# Sheet_1_2023-01-11.net
KiCad netlist of a schematic drawn in Altium Designer
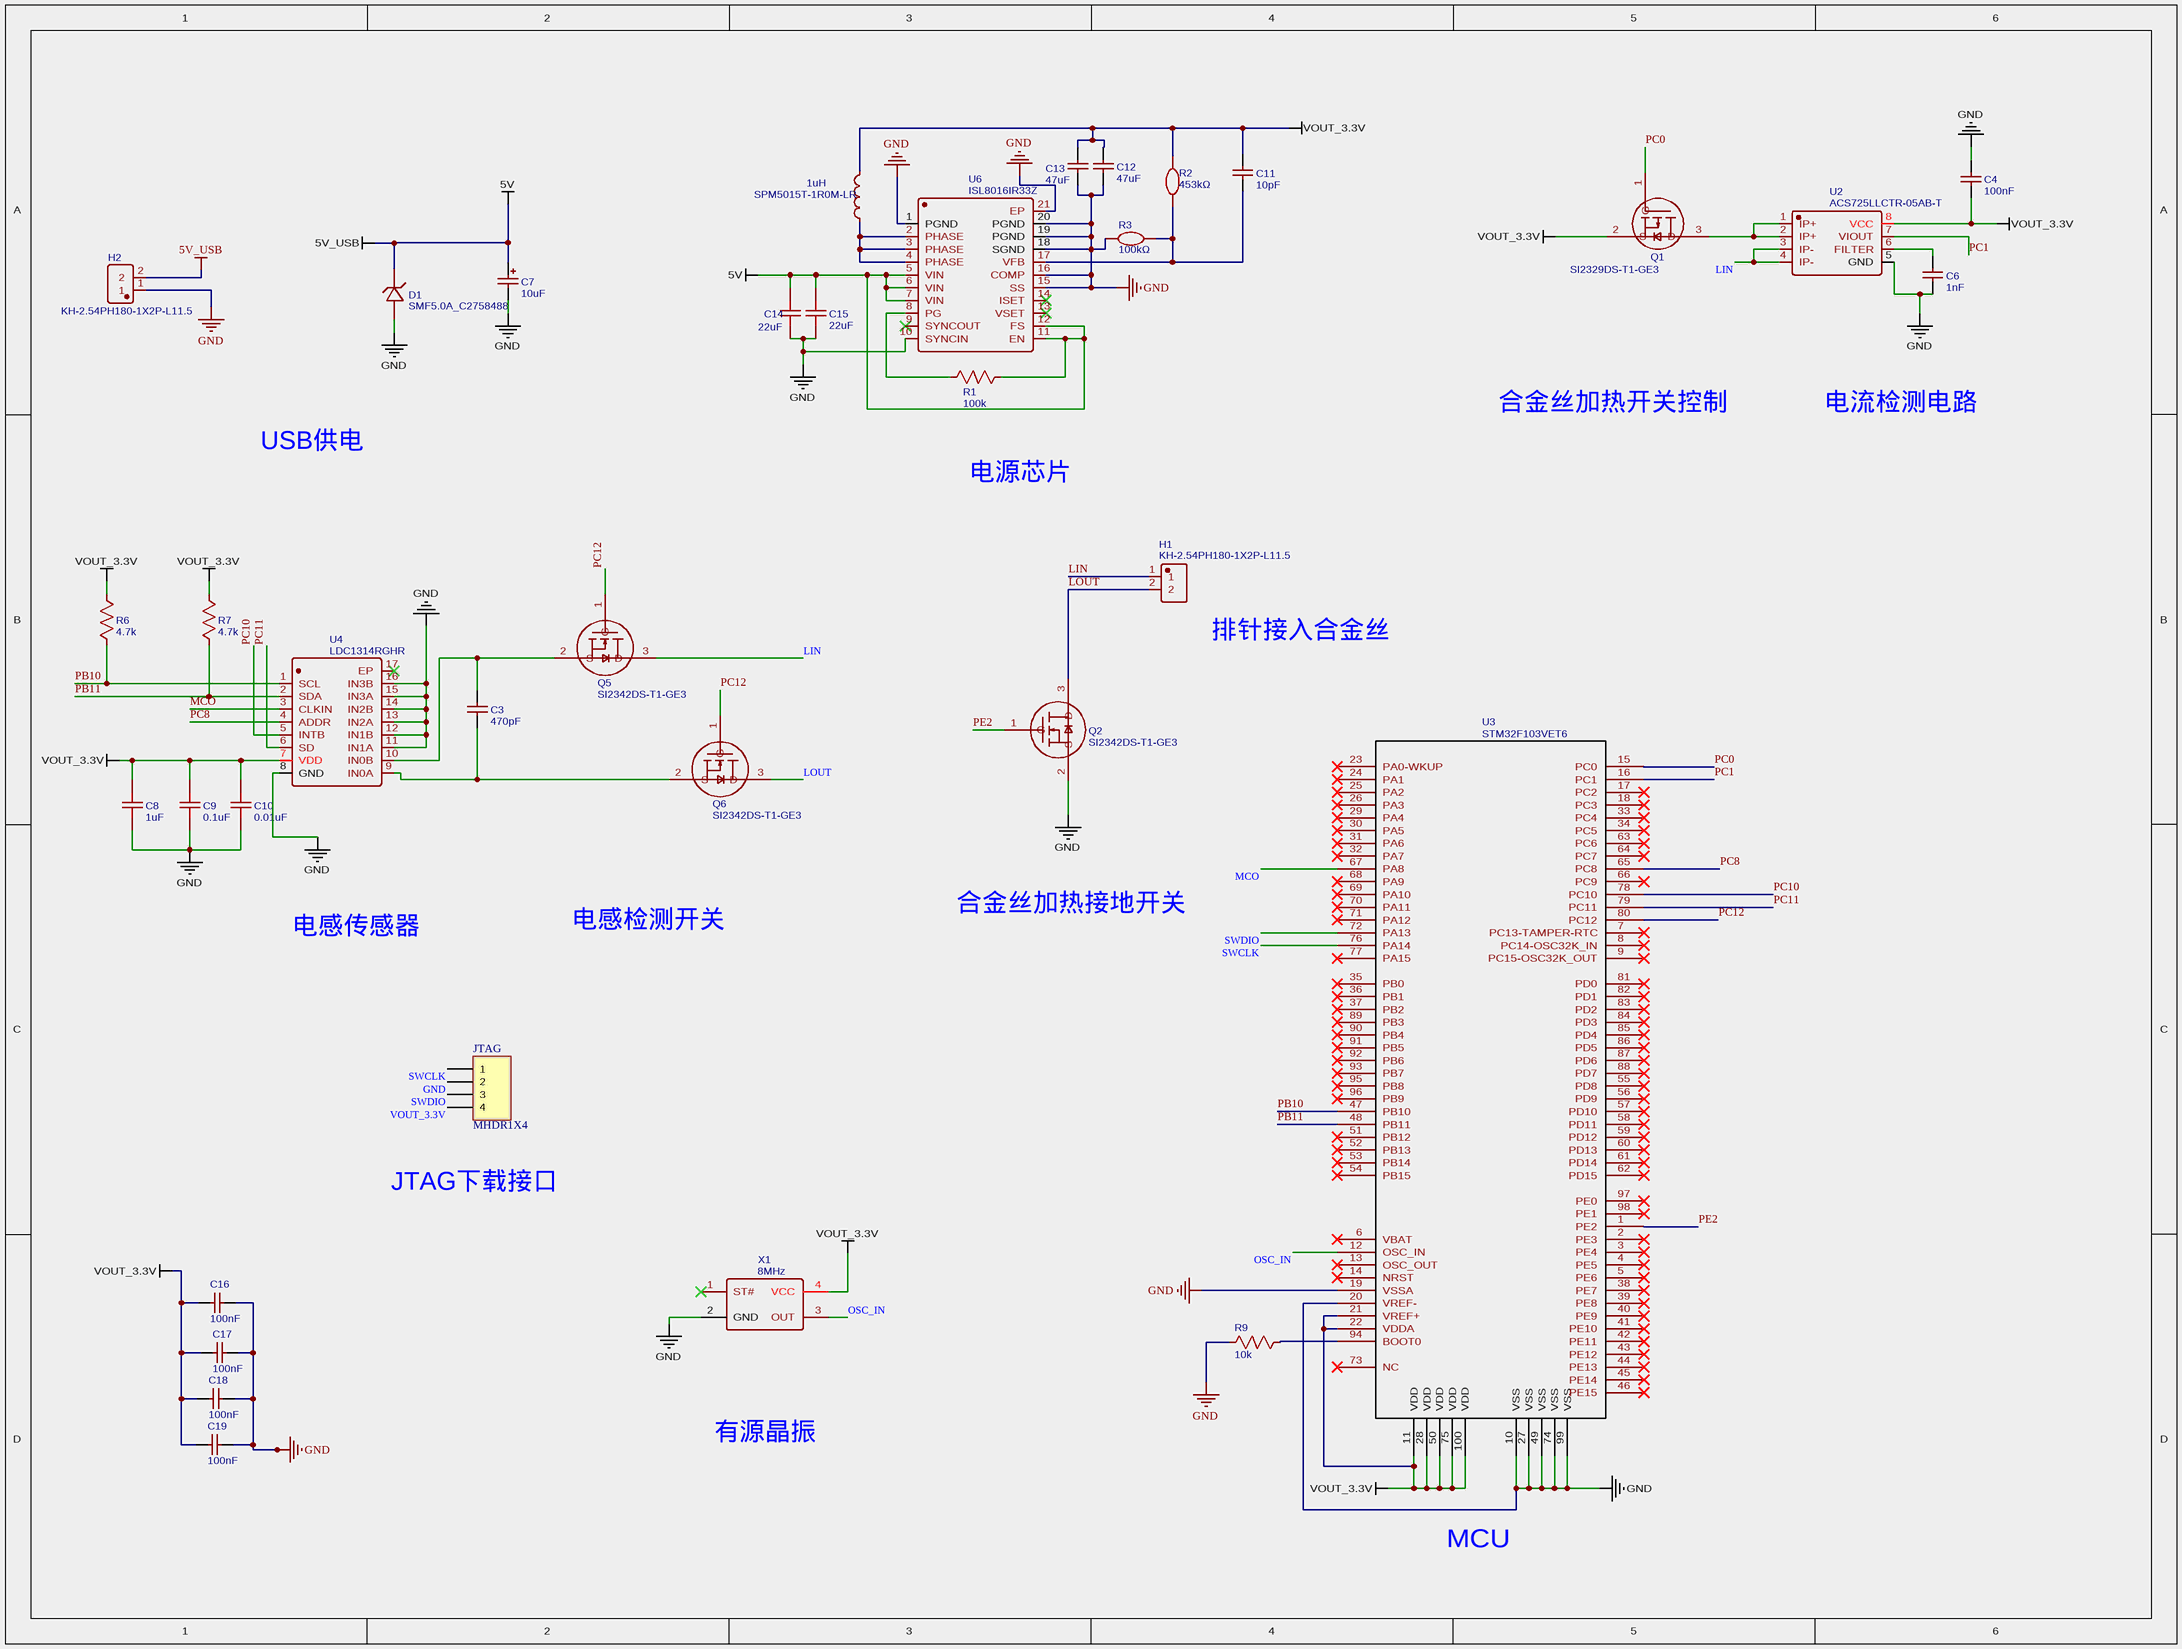
[diagram p0: Sheet_1_2023-01-11.schdoc]

(export (version "E")
  (design (tool "Eeschema 10.0.6"))
  (components
    (comp (ref "1uH")
      (value "SPM5015T-1R0M-LR")
      (footprint "IND-SMD_L5.4-W5.1_SPM5020")
      (fields (field (name "BOM_SUPPLIER PART") "C1329923") (field (name "CONTRIBUTOR") "LCSC"))
      (libsource (lib "altium-import") (part "root_1_SPM5015T-1R0M-LR_"))
    )
    (comp (ref "C3")
      (value "470pF")
      (footprint "C0603")
      (fields
        (field (name "BOM_MANUFACTURER PART") "CC0603KRX7R9BB471")
        (field (name "BOM_SUPPLIER PART") "C107092")
      )
      (libsource (lib "altium-import") (part "root_1_470pF_"))
    )
    (comp (ref "C4")
      (value "100nF")
      (footprint "C0402_NEW")
      (fields
        (field (name "BOM_MANUFACTURER PART") "CL05B104KO5NNNC")
        (field (name "BOM_SUPPLIER PART") "C1525")
      )
      (libsource (lib "altium-import") (part "root_1_100nF_"))
    )
    (comp (ref "C6")
      (value "1nF")
      (footprint "C0603")
      (fields
        (field (name "BOM_MANUFACTURER PART") "CC0603KRX7R9BB102")
        (field (name "BOM_SUPPLIER PART") "C100040")
      )
      (libsource (lib "altium-import") (part "root_1_1nF_"))
    )
    (comp (ref "C7")
      (value "10uF")
      (footprint "CASE-A_3216")
      (fields
        (field (name "BOM_MANUFACTURER PART") "TAJA106K010RNJ")
        (field (name "BOM_SUPPLIER PART") "C7177")
      )
      (libsource (lib "altium-import") (part "root_3_10uF_"))
    )
    (comp (ref "C8")
      (value "1uF")
      (footprint "C0603")
      (fields (field (name "CONTRIBUTOR") "LCEDA_Lib"))
      (libsource (lib "altium-import") (part "root_1_1u_"))
    )
    (comp (ref "C9")
      (value "0.1uF")
      (footprint "C0603")
      (fields (field (name "CONTRIBUTOR") "LCEDA_Lib"))
      (libsource (lib "altium-import") (part "root_1_0.1u_"))
    )
    (comp (ref "C10")
      (value "0.01uF")
      (footprint "C0603")
      (fields (field (name "CONTRIBUTOR") "LCEDA_Lib"))
      (libsource (lib "altium-import") (part "root_1_0.01u_"))
    )
    (comp (ref "C11")
      (value "10pF")
      (footprint "C0402")
      (fields
        (field (name "BOM_MANUFACTURER PART") "CC0402JRNPO9BN100")
        (field (name "BOM_SUPPLIER PART") "C106199")
      )
      (libsource (lib "altium-import") (part "root_3_10pF_"))
    )
    (comp (ref "C12")
      (value "47uF")
      (footprint "C0805")
      (fields
        (field (name "BOM_MANUFACTURER PART") "CL21A476MQYNNNE")
        (field (name "BOM_SUPPLIER PART") "C16780")
      )
      (libsource (lib "altium-import") (part "root_1_47uF_"))
    )
    (comp (ref "C13")
      (value "47uF")
      (footprint "C0805")
      (fields
        (field (name "BOM_MANUFACTURER PART") "CL21A476MQYNNNE")
        (field (name "BOM_SUPPLIER PART") "C16780")
      )
      (libsource (lib "altium-import") (part "root_1_47uF_"))
    )
    (comp (ref "C14")
      (value "22uF")
      (footprint "C0603")
      (fields
        (field (name "BOM_MANUFACTURER PART") "CL10A226MQ8NRNC")
        (field (name "BOM_SUPPLIER PART") "C59461")
      )
      (libsource (lib "altium-import") (part "root_1_22uF_"))
    )
    (comp (ref "C15")
      (value "22uF")
      (footprint "C0603")
      (fields
        (field (name "BOM_MANUFACTURER PART") "CL10A226MQ8NRNC")
        (field (name "BOM_SUPPLIER PART") "C59461")
      )
      (libsource (lib "altium-import") (part "root_1_22uF_"))
    )
    (comp (ref "C16")
      (value "100nF")
      (footprint "C0402_NEW")
      (fields
        (field (name "BOM_MANUFACTURER PART") "CL05B104KO5NNNC")
        (field (name "BOM_SUPPLIER PART") "C1525")
      )
      (libsource (lib "DCDC_schlib_2023-01-11") (part "100nF"))
    )
    (comp (ref "C17")
      (value "100nF")
      (footprint "C0402_NEW")
      (fields
        (field (name "BOM_MANUFACTURER PART") "CL05B104KO5NNNC")
        (field (name "BOM_SUPPLIER PART") "C1525")
      )
      (libsource (lib "DCDC_schlib_2023-01-11") (part "100nF"))
    )
    (comp (ref "C18")
      (value "100nF")
      (footprint "C0402_NEW")
      (fields
        (field (name "BOM_MANUFACTURER PART") "CL05B104KO5NNNC")
        (field (name "BOM_SUPPLIER PART") "C1525")
      )
      (libsource (lib "DCDC_schlib_2023-01-11") (part "100nF"))
    )
    (comp (ref "C19")
      (value "100nF")
      (footprint "C0402_NEW")
      (fields
        (field (name "BOM_MANUFACTURER PART") "CL05B104KO5NNNC")
        (field (name "BOM_SUPPLIER PART") "C1525")
      )
      (libsource (lib "DCDC_schlib_2023-01-11") (part "100nF"))
    )
    (comp (ref "D1")
      (value "SMF5.0A_C2758488")
      (footprint "SOD-123FL_L2.7-W1.8-LS3.7-RD")
      (fields
        (field (name "BOM_SUPPLIER PART") "C2758488")
        (field (name "BOM_MANUFACTURER PART") "SMF5.0A")
        (field (name "CONTRIBUTOR") "LCSC")
      )
      (libsource (lib "altium-import") (part "root_3_SMF5.0A_C2758488_"))
    )
    (comp (ref "H1")
      (value "KH-2.54PH180-1X2P-L11.5")
      (footprint "HDR-TH_2P-P2.54-V-M")
      (fields (field (name "BOM_SUPPLIER PART") "C2905434") (field (name "CONTRIBUTOR") "LCSC"))
      (libsource (lib "altium-import") (part "root_0_KH-2.54PH180-1X2P-L11.5_"))
    )
    (comp (ref "H2")
      (value "KH-2.54PH180-1X2P-L11.5")
      (footprint "HDR-TH_2P-P2.54-V-M")
      (fields (field (name "BOM_SUPPLIER PART") "C2905434") (field (name "CONTRIBUTOR") "LCSC"))
      (libsource (lib "altium-import") (part "root_2_KH-2.54PH180-1X2P-L11.5_"))
    )
    (comp (ref "JTAG")
      (value "MHDR1X4")
      (footprint "MHDR1X4")
      (description "Header, 4-Pin")
      (fields (field (name "PUBLISHER") "Altium Limited"))
      (libsource (lib "Miscellaneous Connectors") (part "MHDR1X4"))
    )
    (comp (ref "Q1")
      (value "SI2329DS-T1-GE3")
      (footprint "SOT-23_L2.9-W1.3-P1.90-LS2.4-BR")
      (fields (field (name "BOM_SUPPLIER PART") "C85167") (field (name "CONTRIBUTOR") "LCSC"))
      (libsource (lib "altium-import") (part "root_3_SI2329DS-T1-GE3_"))
    )
    (comp (ref "Q2")
      (value "SI2342DS-T1-GE3")
      (footprint "SOT-23_L2.9-W1.3-P1.90-LS2.4-BR")
      (fields (field (name "BOM_SUPPLIER PART") "C142553") (field (name "CONTRIBUTOR") "LCSC"))
      (libsource (lib "altium-import") (part "root_0_SI2342DS-T1-GE3_"))
    )
    (comp (ref "Q5")
      (value "SI2342DS-T1-GE3")
      (footprint "SOT-23_L2.9-W1.3-P1.90-LS2.4-BR")
      (fields (field (name "BOM_SUPPLIER PART") "C142553") (field (name "CONTRIBUTOR") "LCSC"))
      (libsource (lib "altium-import") (part "root_3_SI2342DS-T1-GE3_"))
    )
    (comp (ref "Q6")
      (value "SI2342DS-T1-GE3")
      (footprint "SOT-23_L2.9-W1.3-P1.90-LS2.4-BR")
      (fields (field (name "BOM_SUPPLIER PART") "C142553") (field (name "CONTRIBUTOR") "LCSC"))
      (libsource (lib "altium-import") (part "root_3_SI2342DS-T1-GE3_"))
    )
    (comp (ref "R1")
      (value "100k")
      (footprint "R0603")
      (fields (field (name "CONTRIBUTOR") "LCEDA_Lib"))
      (libsource (lib "altium-import") (part "root_0_100k_"))
    )
    (comp (ref "R2")
      (value "453kΩ")
      (footprint "R0402")
      (fields
        (field (name "BOM_SUPPLIER PART") "C407681")
        (field (name "BOM_MANUFACTURER PART") "0402WGF4503TCE")
        (field (name "CONTRIBUTOR") "LCSC")
      )
      (libsource (lib "3") (part "450kΩ"))
    )
    (comp (ref "R3")
      (value "100kΩ")
      (footprint "R0402")
      (fields
        (field (name "BOM_SUPPLIER PART") "C407681")
        (field (name "BOM_MANUFACTURER PART") "0402WGF4503TCE")
        (field (name "CONTRIBUTOR") "LCSC")
      )
      (libsource (lib "3") (part "450kΩ"))
    )
    (comp (ref "R6")
      (value "4.7k")
      (footprint "R0603")
      (fields (field (name "CONTRIBUTOR") "LCEDA_Lib"))
      (libsource (lib "altium-import") (part "root_1_4.7k_"))
    )
    (comp (ref "R7")
      (value "4.7k")
      (footprint "R0603")
      (fields (field (name "CONTRIBUTOR") "LCEDA_Lib"))
      (libsource (lib "altium-import") (part "root_1_4.7k_"))
    )
    (comp (ref "R9")
      (value "10k")
      (footprint "R0603")
      (fields (field (name "CONTRIBUTOR") "LCEDA_Lib"))
      (libsource (lib "T1") (part "10k"))
    )
    (comp (ref "U2")
      (value "ACS725LLCTR-05AB-T")
      (footprint "SOIC-8_L5.0-W4.0-P1.27-LS6.1-BL")
      (fields (field (name "BOM_SUPPLIER PART") "C3684552") (field (name "CONTRIBUTOR") "lcsc"))
      (libsource (lib "altium-import") (part "root_0_ACS725LLCTR-05AB-T_"))
    )
    (comp (ref "U3")
      (value "STM32F103VET6")
      (footprint "LQFP-100_L14.0-W14.0-P0.50-LS16.0-BL")
      (fields (field (name "BOM_SUPPLIER PART") "C8308"))
      (libsource (lib "altium-import") (part "root_0_STM32F103VET6_"))
    )
    (comp (ref "U4")
      (value "LDC1314RGHR")
      (footprint "QFN-16_L4.0-W4.0-P0.50-TL-EP2.4")
      (fields (field (name "BOM_SUPPLIER PART") "C2667027") (field (name "CONTRIBUTOR") "LCSC"))
      (libsource (lib "altium-import") (part "root_0_LDC1314RGHR_"))
    )
    (comp (ref "U6")
      (value "ISL8016IR33Z")
      (footprint "QFN-20_L4.0-W3.0-P0.5-TL-EP2.7")
      (fields (field (name "BOM_SUPPLIER PART") "C1356368") (field (name "CONTRIBUTOR") "lcsc"))
      (libsource (lib "altium-import") (part "root_0_ISL8016IR33Z_"))
    )
    (comp (ref "X1")
      (value "8MHz")
      (footprint "OSC-SMD_4P-L3.2-W2.5-BL")
      (fields
        (field (name "BOM_MANUFACTURER PART") "Q33310F70055100")
        (field (name "BOM_SUPPLIER PART") "C70556")
      )
      (libsource (lib "altium-import") (part "root_0_8MHz_"))
    )
  )
  (nets
    (net (code "1") (name "/LIN") (class "Default")
      (node (ref "H1") (pin "1") (pinfunction "1_1") (pintype "passive"))
      (node (ref "Q5") (pin "3") (pinfunction "D_3") (pintype "passive"))
      (node (ref "U2") (pin "3") (pinfunction "IP-_3") (pintype "passive"))
      (node (ref "U2") (pin "4") (pinfunction "IP-_4") (pintype "passive"))
    )
    (net (code "2") (name "/LOUT") (class "Default")
      (node (ref "H1") (pin "2") (pinfunction "2_2") (pintype "passive"))
      (node (ref "Q2") (pin "3") (pinfunction "D_3") (pintype "passive"))
      (node (ref "Q6") (pin "3") (pinfunction "D_3") (pintype "passive"))
    )
    (net (code "3") (name "/MCO") (class "Default")
      (node (ref "U3") (pin "67") (pinfunction "PA8_67") (pintype "passive"))
      (node (ref "U4") (pin "3") (pinfunction "CLKIN_3") (pintype "passive"))
    )
    (net (code "4") (name "/OSC_IN") (class "Default")
      (node (ref "U3") (pin "12") (pinfunction "OSC_IN_12") (pintype "passive"))
      (node (ref "X1") (pin "3") (pinfunction "OUT_3") (pintype "passive"))
    )
    (net (code "5") (name "/PB10") (class "Default")
      (node (ref "R6") (pin "1") (pinfunction "1_1") (pintype "passive"))
      (node (ref "U3") (pin "47") (pinfunction "PB10_47") (pintype "passive"))
      (node (ref "U4") (pin "1") (pinfunction "SCL_1") (pintype "passive"))
    )
    (net (code "6") (name "/PB11") (class "Default")
      (node (ref "R7") (pin "1") (pinfunction "1_1") (pintype "passive"))
      (node (ref "U3") (pin "48") (pinfunction "PB11_48") (pintype "passive"))
      (node (ref "U4") (pin "2") (pinfunction "SDA_2") (pintype "passive"))
    )
    (net (code "7") (name "/PC0") (class "Default")
      (node (ref "Q1") (pin "1") (pinfunction "G_1") (pintype "passive"))
      (node (ref "U3") (pin "15") (pinfunction "PC0_15") (pintype "passive"))
    )
    (net (code "8") (name "/PC1") (class "Default")
      (node (ref "U2") (pin "7") (pinfunction "VIOUT_7") (pintype "passive"))
      (node (ref "U3") (pin "16") (pinfunction "PC1_16") (pintype "passive"))
    )
    (net (code "9") (name "/PC8") (class "Default")
      (node (ref "U3") (pin "65") (pinfunction "PC8_65") (pintype "passive"))
      (node (ref "U4") (pin "4") (pinfunction "ADDR_4") (pintype "passive"))
    )
    (net (code "10") (name "/PC10") (class "Default")
      (node (ref "U3") (pin "78") (pinfunction "PC10_78") (pintype "passive"))
      (node (ref "U4") (pin "5") (pinfunction "INTB_5") (pintype "passive"))
    )
    (net (code "11") (name "/PC11") (class "Default")
      (node (ref "U3") (pin "79") (pinfunction "PC11_79") (pintype "passive"))
      (node (ref "U4") (pin "6") (pinfunction "SD_6") (pintype "passive"))
    )
    (net (code "12") (name "/PC12") (class "Default")
      (node (ref "Q5") (pin "1") (pinfunction "G_1") (pintype "passive"))
      (node (ref "Q6") (pin "1") (pinfunction "G_1") (pintype "passive"))
      (node (ref "U3") (pin "80") (pinfunction "PC12_80") (pintype "passive"))
    )
    (net (code "13") (name "/PE2") (class "Default")
      (node (ref "Q2") (pin "1") (pinfunction "G_1") (pintype "passive"))
      (node (ref "U3") (pin "1") (pinfunction "PE2_1") (pintype "passive"))
    )
    (net (code "14") (name "/SWCLK") (class "Default")
      (node (ref "JTAG") (pin "1") (pinfunction "1_1") (pintype "passive"))
      (node (ref "U3") (pin "76") (pinfunction "PA14_76") (pintype "passive"))
    )
    (net (code "15") (name "/SWDIO") (class "Default")
      (node (ref "JTAG") (pin "3") (pinfunction "3_3") (pintype "passive"))
      (node (ref "U3") (pin "72") (pinfunction "PA13_72") (pintype "passive"))
    )
    (net (code "16") (name "5V") (class "Default")
      (node (ref "C14") (pin "2") (pinfunction "2_2") (pintype "passive"))
      (node (ref "C15") (pin "2") (pinfunction "2_2") (pintype "passive"))
      (node (ref "C7") (pin "1") (pinfunction "1_1") (pintype "passive"))
      (node (ref "D1") (pin "1") (pinfunction "C_1") (pintype "passive"))
      (node (ref "H2") (pin "2") (pinfunction "2_2") (pintype "passive"))
      (node (ref "R1") (pin "2") (pinfunction "2_2") (pintype "passive"))
      (node (ref "U6") (pin "11") (pinfunction "EN_11") (pintype "passive"))
      (node (ref "U6") (pin "12") (pinfunction "FS_12") (pintype "passive"))
      (node (ref "U6") (pin "5") (pinfunction "VIN_5") (pintype "passive"))
      (node (ref "U6") (pin "6") (pinfunction "VIN_6") (pintype "passive"))
      (node (ref "U6") (pin "7") (pinfunction "VIN_7") (pintype "passive"))
    )
    (net (code "17") (name "GND") (class "Default")
      (node (ref "C10") (pin "1") (pinfunction "1_1") (pintype "passive"))
      (node (ref "C12") (pin "1") (pinfunction "1_1") (pintype "passive"))
      (node (ref "C13") (pin "1") (pinfunction "1_1") (pintype "passive"))
      (node (ref "C14") (pin "1") (pinfunction "1_1") (pintype "passive"))
      (node (ref "C15") (pin "1") (pinfunction "1_1") (pintype "passive"))
      (node (ref "C16") (pin "1") (pinfunction "1_1") (pintype "passive"))
      (node (ref "C17") (pin "1") (pinfunction "1_1") (pintype "passive"))
      (node (ref "C18") (pin "1") (pinfunction "1_1") (pintype "passive"))
      (node (ref "C19") (pin "2") (pinfunction "2_2") (pintype "passive"))
      (node (ref "C4") (pin "2") (pinfunction "2_2") (pintype "passive"))
      (node (ref "C6") (pin "1") (pinfunction "1_1") (pintype "passive"))
      (node (ref "C7") (pin "2") (pinfunction "2_2") (pintype "passive"))
      (node (ref "C8") (pin "1") (pinfunction "1_1") (pintype "passive"))
      (node (ref "C9") (pin "1") (pinfunction "1_1") (pintype "passive"))
      (node (ref "D1") (pin "2") (pinfunction "A_2") (pintype "passive"))
      (node (ref "H2") (pin "1") (pinfunction "1_1") (pintype "passive"))
      (node (ref "JTAG") (pin "2") (pinfunction "2_2") (pintype "passive"))
      (node (ref "Q2") (pin "2") (pinfunction "S_2") (pintype "passive"))
      (node (ref "R3") (pin "1") (pinfunction "1_1") (pintype "passive"))
      (node (ref "R9") (pin "1") (pinfunction "1_1") (pintype "passive"))
      (node (ref "U2") (pin "5") (pinfunction "GND_5") (pintype "passive"))
      (node (ref "U3") (pin "10") (pinfunction "VSS_10") (pintype "passive"))
      (node (ref "U3") (pin "19") (pinfunction "VSSA_19") (pintype "passive"))
      (node (ref "U3") (pin "20") (pinfunction "VREF-_20") (pintype "passive"))
      (node (ref "U3") (pin "27") (pinfunction "VSS_27") (pintype "passive"))
      (node (ref "U3") (pin "49") (pinfunction "VSS_49") (pintype "passive"))
      (node (ref "U3") (pin "74") (pinfunction "VSS_74") (pintype "passive"))
      (node (ref "U3") (pin "99") (pinfunction "VSS_99") (pintype "passive"))
      (node (ref "U4") (pin "11") (pinfunction "IN1A_11") (pintype "passive"))
      (node (ref "U4") (pin "12") (pinfunction "IN1B_12") (pintype "passive"))
      (node (ref "U4") (pin "13") (pinfunction "IN2A_13") (pintype "passive"))
      (node (ref "U4") (pin "14") (pinfunction "IN2B_14") (pintype "passive"))
      (node (ref "U4") (pin "15") (pinfunction "IN3A_15") (pintype "passive"))
      (node (ref "U4") (pin "16") (pinfunction "IN3B_16") (pintype "passive"))
      (node (ref "U4") (pin "8") (pinfunction "GND_8") (pintype "passive"))
      (node (ref "U6") (pin "1") (pinfunction "PGND_1") (pintype "passive"))
      (node (ref "U6") (pin "10") (pinfunction "SYNCIN_10") (pintype "passive"))
      (node (ref "U6") (pin "15") (pinfunction "SS_15") (pintype "passive"))
      (node (ref "U6") (pin "16") (pinfunction "COMP_16") (pintype "passive"))
      (node (ref "U6") (pin "18") (pinfunction "SGND_18") (pintype "passive"))
      (node (ref "U6") (pin "19") (pinfunction "PGND_19") (pintype "passive"))
      (node (ref "U6") (pin "20") (pinfunction "PGND_20") (pintype "passive"))
      (node (ref "U6") (pin "21") (pinfunction "EP_21") (pintype "passive"))
      (node (ref "X1") (pin "2") (pinfunction "GND_2") (pintype "passive"))
    )
    (net (code "18") (name "Net-(1uH-Pad1)") (class "Default")
      (node (ref "1uH") (pin "1") (pinfunction "1_1") (pintype "passive"))
      (node (ref "U6") (pin "2") (pinfunction "PHASE_2") (pintype "passive"))
      (node (ref "U6") (pin "3") (pinfunction "PHASE_3") (pintype "passive"))
      (node (ref "U6") (pin "4") (pinfunction "PHASE_4") (pintype "passive"))
    )
    (net (code "19") (name "Net-(Q1-D)") (class "Default")
      (node (ref "Q1") (pin "3") (pinfunction "D_3") (pintype "passive"))
      (node (ref "U2") (pin "1") (pinfunction "IP+_1") (pintype "passive"))
      (node (ref "U2") (pin "2") (pinfunction "IP+_2") (pintype "passive"))
    )
    (net (code "20") (name "Net-(Q5-S)") (class "Default")
      (node (ref "C3") (pin "2") (pinfunction "2_2") (pintype "passive"))
      (node (ref "Q5") (pin "2") (pinfunction "S_2") (pintype "passive"))
      (node (ref "U4") (pin "10") (pinfunction "IN0B_10") (pintype "passive"))
    )
    (net (code "21") (name "Net-(Q6-S)") (class "Default")
      (node (ref "C3") (pin "1") (pinfunction "1_1") (pintype "passive"))
      (node (ref "Q6") (pin "2") (pinfunction "S_2") (pintype "passive"))
      (node (ref "U4") (pin "9") (pinfunction "IN0A_9") (pintype "passive"))
    )
    (net (code "22") (name "Net-(U2-FILTER)") (class "Default")
      (node (ref "C6") (pin "2") (pinfunction "2_2") (pintype "passive"))
      (node (ref "U2") (pin "6") (pinfunction "FILTER_6") (pintype "passive"))
    )
    (net (code "23") (name "Net-(U3-BOOT0)") (class "Default")
      (node (ref "R9") (pin "2") (pinfunction "2_2") (pintype "passive"))
      (node (ref "U3") (pin "94") (pinfunction "BOOT0_94") (pintype "passive"))
    )
    (net (code "24") (name "Net-(U6-PG)") (class "Default")
      (node (ref "R1") (pin "1") (pinfunction "1_1") (pintype "passive"))
      (node (ref "U6") (pin "8") (pinfunction "PG_8") (pintype "passive"))
    )
    (net (code "25") (name "Net-(U6-VFB)") (class "Default")
      (node (ref "C11") (pin "2") (pinfunction "2_2") (pintype "passive"))
      (node (ref "R2") (pin "1") (pinfunction "1_1") (pintype "passive"))
      (node (ref "R3") (pin "2") (pinfunction "2_2") (pintype "passive"))
      (node (ref "U6") (pin "17") (pinfunction "VFB_17") (pintype "passive"))
    )
    (net (code "26") (name "VOUT_3.3V") (class "Default")
      (node (ref "1uH") (pin "2") (pinfunction "2_2") (pintype "passive"))
      (node (ref "C10") (pin "2") (pinfunction "2_2") (pintype "passive"))
      (node (ref "C11") (pin "1") (pinfunction "1_1") (pintype "passive"))
      (node (ref "C12") (pin "2") (pinfunction "2_2") (pintype "passive"))
      (node (ref "C13") (pin "2") (pinfunction "2_2") (pintype "passive"))
      (node (ref "C16") (pin "2") (pinfunction "2_2") (pintype "passive"))
      (node (ref "C17") (pin "2") (pinfunction "2_2") (pintype "passive"))
      (node (ref "C18") (pin "2") (pinfunction "2_2") (pintype "passive"))
      (node (ref "C19") (pin "1") (pinfunction "1_1") (pintype "passive"))
      (node (ref "C4") (pin "1") (pinfunction "1_1") (pintype "passive"))
      (node (ref "C8") (pin "2") (pinfunction "2_2") (pintype "passive"))
      (node (ref "C9") (pin "2") (pinfunction "2_2") (pintype "passive"))
      (node (ref "JTAG") (pin "4") (pinfunction "4_4") (pintype "passive"))
      (node (ref "Q1") (pin "2") (pinfunction "S_2") (pintype "passive"))
      (node (ref "R2") (pin "2") (pinfunction "2_2") (pintype "passive"))
      (node (ref "R6") (pin "2") (pinfunction "2_2") (pintype "passive"))
      (node (ref "R7") (pin "2") (pinfunction "2_2") (pintype "passive"))
      (node (ref "U2") (pin "8") (pinfunction "VCC_8") (pintype "passive"))
      (node (ref "U3") (pin "100") (pinfunction "VDD_100") (pintype "passive"))
      (node (ref "U3") (pin "11") (pinfunction "VDD_11") (pintype "passive"))
      (node (ref "U3") (pin "21") (pinfunction "VREF+_21") (pintype "passive"))
      (node (ref "U3") (pin "22") (pinfunction "VDDA_22") (pintype "passive"))
      (node (ref "U3") (pin "28") (pinfunction "VDD_28") (pintype "passive"))
      (node (ref "U3") (pin "50") (pinfunction "VDD_50") (pintype "passive"))
      (node (ref "U3") (pin "75") (pinfunction "VDD_75") (pintype "passive"))
      (node (ref "U4") (pin "7") (pinfunction "VDD_7") (pintype "passive"))
      (node (ref "X1") (pin "4") (pinfunction "VCC_4") (pintype "passive"))
    )
    (net (code "27") (name "unconnected-(U3-NC-Pad73)") (class "Default")
      (node (ref "U3") (pin "73") (pinfunction "NC_73") (pintype "passive+no_connect"))
    )
    (net (code "28") (name "unconnected-(U3-NRST-Pad14)") (class "Default")
      (node (ref "U3") (pin "14") (pinfunction "NRST_14") (pintype "passive+no_connect"))
    )
    (net (code "29") (name "unconnected-(U3-OSC_OUT-Pad13)") (class "Default")
      (node (ref "U3") (pin "13") (pinfunction "OSC_OUT_13") (pintype "passive+no_connect"))
    )
    (net (code "30") (name "unconnected-(U3-PA0-WKUP-Pad23)") (class "Default")
      (node (ref "U3") (pin "23") (pinfunction "PA0-WKUP_23") (pintype "passive+no_connect"))
    )
    (net (code "31") (name "unconnected-(U3-PA1-Pad24)") (class "Default")
      (node (ref "U3") (pin "24") (pinfunction "PA1_24") (pintype "passive+no_connect"))
    )
    (net (code "32") (name "unconnected-(U3-PA2-Pad25)") (class "Default")
      (node (ref "U3") (pin "25") (pinfunction "PA2_25") (pintype "passive+no_connect"))
    )
    (net (code "33") (name "unconnected-(U3-PA3-Pad26)") (class "Default")
      (node (ref "U3") (pin "26") (pinfunction "PA3_26") (pintype "passive+no_connect"))
    )
    (net (code "34") (name "unconnected-(U3-PA4-Pad29)") (class "Default")
      (node (ref "U3") (pin "29") (pinfunction "PA4_29") (pintype "passive+no_connect"))
    )
    (net (code "35") (name "unconnected-(U3-PA5-Pad30)") (class "Default")
      (node (ref "U3") (pin "30") (pinfunction "PA5_30") (pintype "passive+no_connect"))
    )
    (net (code "36") (name "unconnected-(U3-PA6-Pad31)") (class "Default")
      (node (ref "U3") (pin "31") (pinfunction "PA6_31") (pintype "passive+no_connect"))
    )
    (net (code "37") (name "unconnected-(U3-PA7-Pad32)") (class "Default")
      (node (ref "U3") (pin "32") (pinfunction "PA7_32") (pintype "passive+no_connect"))
    )
    (net (code "38") (name "unconnected-(U3-PA9-Pad68)") (class "Default")
      (node (ref "U3") (pin "68") (pinfunction "PA9_68") (pintype "passive+no_connect"))
    )
    (net (code "39") (name "unconnected-(U3-PA10-Pad69)") (class "Default")
      (node (ref "U3") (pin "69") (pinfunction "PA10_69") (pintype "passive+no_connect"))
    )
    (net (code "40") (name "unconnected-(U3-PA11-Pad70)") (class "Default")
      (node (ref "U3") (pin "70") (pinfunction "PA11_70") (pintype "passive+no_connect"))
    )
    (net (code "41") (name "unconnected-(U3-PA12-Pad71)") (class "Default")
      (node (ref "U3") (pin "71") (pinfunction "PA12_71") (pintype "passive+no_connect"))
    )
    (net (code "42") (name "unconnected-(U3-PA15-Pad77)") (class "Default")
      (node (ref "U3") (pin "77") (pinfunction "PA15_77") (pintype "passive+no_connect"))
    )
    (net (code "43") (name "unconnected-(U3-PB0-Pad35)") (class "Default")
      (node (ref "U3") (pin "35") (pinfunction "PB0_35") (pintype "passive+no_connect"))
    )
    (net (code "44") (name "unconnected-(U3-PB1-Pad36)") (class "Default")
      (node (ref "U3") (pin "36") (pinfunction "PB1_36") (pintype "passive+no_connect"))
    )
    (net (code "45") (name "unconnected-(U3-PB2-Pad37)") (class "Default")
      (node (ref "U3") (pin "37") (pinfunction "PB2_37") (pintype "passive+no_connect"))
    )
    (net (code "46") (name "unconnected-(U3-PB3-Pad89)") (class "Default")
      (node (ref "U3") (pin "89") (pinfunction "PB3_89") (pintype "passive+no_connect"))
    )
    (net (code "47") (name "unconnected-(U3-PB4-Pad90)") (class "Default")
      (node (ref "U3") (pin "90") (pinfunction "PB4_90") (pintype "passive+no_connect"))
    )
    (net (code "48") (name "unconnected-(U3-PB5-Pad91)") (class "Default")
      (node (ref "U3") (pin "91") (pinfunction "PB5_91") (pintype "passive+no_connect"))
    )
    (net (code "49") (name "unconnected-(U3-PB6-Pad92)") (class "Default")
      (node (ref "U3") (pin "92") (pinfunction "PB6_92") (pintype "passive+no_connect"))
    )
    (net (code "50") (name "unconnected-(U3-PB7-Pad93)") (class "Default")
      (node (ref "U3") (pin "93") (pinfunction "PB7_93") (pintype "passive+no_connect"))
    )
    (net (code "51") (name "unconnected-(U3-PB8-Pad95)") (class "Default")
      (node (ref "U3") (pin "95") (pinfunction "PB8_95") (pintype "passive+no_connect"))
    )
    (net (code "52") (name "unconnected-(U3-PB9-Pad96)") (class "Default")
      (node (ref "U3") (pin "96") (pinfunction "PB9_96") (pintype "passive+no_connect"))
    )
    (net (code "53") (name "unconnected-(U3-PB12-Pad51)") (class "Default")
      (node (ref "U3") (pin "51") (pinfunction "PB12_51") (pintype "passive+no_connect"))
    )
    (net (code "54") (name "unconnected-(U3-PB13-Pad52)") (class "Default")
      (node (ref "U3") (pin "52") (pinfunction "PB13_52") (pintype "passive+no_connect"))
    )
    (net (code "55") (name "unconnected-(U3-PB14-Pad53)") (class "Default")
      (node (ref "U3") (pin "53") (pinfunction "PB14_53") (pintype "passive+no_connect"))
    )
    (net (code "56") (name "unconnected-(U3-PB15-Pad54)") (class "Default")
      (node (ref "U3") (pin "54") (pinfunction "PB15_54") (pintype "passive+no_connect"))
    )
    (net (code "57") (name "unconnected-(U3-PC2-Pad17)") (class "Default")
      (node (ref "U3") (pin "17") (pinfunction "PC2_17") (pintype "passive+no_connect"))
    )
    (net (code "58") (name "unconnected-(U3-PC3-Pad18)") (class "Default")
      (node (ref "U3") (pin "18") (pinfunction "PC3_18") (pintype "passive+no_connect"))
    )
    (net (code "59") (name "unconnected-(U3-PC4-Pad33)") (class "Default")
      (node (ref "U3") (pin "33") (pinfunction "PC4_33") (pintype "passive+no_connect"))
    )
    (net (code "60") (name "unconnected-(U3-PC5-Pad34)") (class "Default")
      (node (ref "U3") (pin "34") (pinfunction "PC5_34") (pintype "passive+no_connect"))
    )
    (net (code "61") (name "unconnected-(U3-PC6-Pad63)") (class "Default")
      (node (ref "U3") (pin "63") (pinfunction "PC6_63") (pintype "passive+no_connect"))
    )
    (net (code "62") (name "unconnected-(U3-PC7-Pad64)") (class "Default")
      (node (ref "U3") (pin "64") (pinfunction "PC7_64") (pintype "passive+no_connect"))
    )
    (net (code "63") (name "unconnected-(U3-PC9-Pad66)") (class "Default")
      (node (ref "U3") (pin "66") (pinfunction "PC9_66") (pintype "passive+no_connect"))
    )
    (net (code "64") (name "unconnected-(U3-PC13-TAMPER-RTC-Pad7)") (class "Default")
      (node (ref "U3") (pin "7") (pinfunction "PC13-TAMPER-RTC_7") (pintype "passive+no_connect"))
    )
    (net (code "65") (name "unconnected-(U3-PC14-OSC32K_IN-Pad8)") (class "Default")
      (node (ref "U3") (pin "8") (pinfunction "PC14-OSC32K_IN_8") (pintype "passive+no_connect"))
    )
    (net (code "66") (name "unconnected-(U3-PC15-OSC32K_OUT-Pad9)") (class "Default")
      (node (ref "U3") (pin "9") (pinfunction "PC15-OSC32K_OUT_9") (pintype "passive+no_connect"))
    )
    (net (code "67") (name "unconnected-(U3-PD0-Pad81)") (class "Default")
      (node (ref "U3") (pin "81") (pinfunction "PD0_81") (pintype "passive+no_connect"))
    )
    (net (code "68") (name "unconnected-(U3-PD1-Pad82)") (class "Default")
      (node (ref "U3") (pin "82") (pinfunction "PD1_82") (pintype "passive+no_connect"))
    )
    (net (code "69") (name "unconnected-(U3-PD2-Pad83)") (class "Default")
      (node (ref "U3") (pin "83") (pinfunction "PD2_83") (pintype "passive+no_connect"))
    )
    (net (code "70") (name "unconnected-(U3-PD3-Pad84)") (class "Default")
      (node (ref "U3") (pin "84") (pinfunction "PD3_84") (pintype "passive+no_connect"))
    )
    (net (code "71") (name "unconnected-(U3-PD4-Pad85)") (class "Default")
      (node (ref "U3") (pin "85") (pinfunction "PD4_85") (pintype "passive+no_connect"))
    )
    (net (code "72") (name "unconnected-(U3-PD5-Pad86)") (class "Default")
      (node (ref "U3") (pin "86") (pinfunction "PD5_86") (pintype "passive+no_connect"))
    )
    (net (code "73") (name "unconnected-(U3-PD6-Pad87)") (class "Default")
      (node (ref "U3") (pin "87") (pinfunction "PD6_87") (pintype "passive+no_connect"))
    )
    (net (code "74") (name "unconnected-(U3-PD7-Pad88)") (class "Default")
      (node (ref "U3") (pin "88") (pinfunction "PD7_88") (pintype "passive+no_connect"))
    )
    (net (code "75") (name "unconnected-(U3-PD8-Pad55)") (class "Default")
      (node (ref "U3") (pin "55") (pinfunction "PD8_55") (pintype "passive+no_connect"))
    )
    (net (code "76") (name "unconnected-(U3-PD9-Pad56)") (class "Default")
      (node (ref "U3") (pin "56") (pinfunction "PD9_56") (pintype "passive+no_connect"))
    )
    (net (code "77") (name "unconnected-(U3-PD10-Pad57)") (class "Default")
      (node (ref "U3") (pin "57") (pinfunction "PD10_57") (pintype "passive+no_connect"))
    )
    (net (code "78") (name "unconnected-(U3-PD11-Pad58)") (class "Default")
      (node (ref "U3") (pin "58") (pinfunction "PD11_58") (pintype "passive+no_connect"))
    )
    (net (code "79") (name "unconnected-(U3-PD12-Pad59)") (class "Default")
      (node (ref "U3") (pin "59") (pinfunction "PD12_59") (pintype "passive+no_connect"))
    )
    (net (code "80") (name "unconnected-(U3-PD13-Pad60)") (class "Default")
      (node (ref "U3") (pin "60") (pinfunction "PD13_60") (pintype "passive+no_connect"))
    )
    (net (code "81") (name "unconnected-(U3-PD14-Pad61)") (class "Default")
      (node (ref "U3") (pin "61") (pinfunction "PD14_61") (pintype "passive+no_connect"))
    )
    (net (code "82") (name "unconnected-(U3-PD15-Pad62)") (class "Default")
      (node (ref "U3") (pin "62") (pinfunction "PD15_62") (pintype "passive+no_connect"))
    )
    (net (code "83") (name "unconnected-(U3-PE0-Pad97)") (class "Default")
      (node (ref "U3") (pin "97") (pinfunction "PE0_97") (pintype "passive+no_connect"))
    )
    (net (code "84") (name "unconnected-(U3-PE1-Pad98)") (class "Default")
      (node (ref "U3") (pin "98") (pinfunction "PE1_98") (pintype "passive+no_connect"))
    )
    (net (code "85") (name "unconnected-(U3-PE3-Pad2)") (class "Default")
      (node (ref "U3") (pin "2") (pinfunction "PE3_2") (pintype "passive+no_connect"))
    )
    (net (code "86") (name "unconnected-(U3-PE4-Pad3)") (class "Default")
      (node (ref "U3") (pin "3") (pinfunction "PE4_3") (pintype "passive+no_connect"))
    )
    (net (code "87") (name "unconnected-(U3-PE5-Pad4)") (class "Default")
      (node (ref "U3") (pin "4") (pinfunction "PE5_4") (pintype "passive+no_connect"))
    )
    (net (code "88") (name "unconnected-(U3-PE6-Pad5)") (class "Default")
      (node (ref "U3") (pin "5") (pinfunction "PE6_5") (pintype "passive+no_connect"))
    )
    (net (code "89") (name "unconnected-(U3-PE7-Pad38)") (class "Default")
      (node (ref "U3") (pin "38") (pinfunction "PE7_38") (pintype "passive+no_connect"))
    )
    (net (code "90") (name "unconnected-(U3-PE8-Pad39)") (class "Default")
      (node (ref "U3") (pin "39") (pinfunction "PE8_39") (pintype "passive+no_connect"))
    )
    (net (code "91") (name "unconnected-(U3-PE9-Pad40)") (class "Default")
      (node (ref "U3") (pin "40") (pinfunction "PE9_40") (pintype "passive+no_connect"))
    )
    (net (code "92") (name "unconnected-(U3-PE10-Pad41)") (class "Default")
      (node (ref "U3") (pin "41") (pinfunction "PE10_41") (pintype "passive+no_connect"))
    )
    (net (code "93") (name "unconnected-(U3-PE11-Pad42)") (class "Default")
      (node (ref "U3") (pin "42") (pinfunction "PE11_42") (pintype "passive+no_connect"))
    )
    (net (code "94") (name "unconnected-(U3-PE12-Pad43)") (class "Default")
      (node (ref "U3") (pin "43") (pinfunction "PE12_43") (pintype "passive+no_connect"))
    )
    (net (code "95") (name "unconnected-(U3-PE13-Pad44)") (class "Default")
      (node (ref "U3") (pin "44") (pinfunction "PE13_44") (pintype "passive+no_connect"))
    )
    (net (code "96") (name "unconnected-(U3-PE14-Pad45)") (class "Default")
      (node (ref "U3") (pin "45") (pinfunction "PE14_45") (pintype "passive+no_connect"))
    )
    (net (code "97") (name "unconnected-(U3-PE15-Pad46)") (class "Default")
      (node (ref "U3") (pin "46") (pinfunction "PE15_46") (pintype "passive+no_connect"))
    )
    (net (code "98") (name "unconnected-(U3-VBAT-Pad6)") (class "Default")
      (node (ref "U3") (pin "6") (pinfunction "VBAT_6") (pintype "passive+no_connect"))
    )
    (net (code "99") (name "unconnected-(U4-EP-Pad17)") (class "Default")
      (node (ref "U4") (pin "17") (pinfunction "EP_17") (pintype "passive+no_connect"))
    )
    (net (code "100") (name "unconnected-(U6-ISET-Pad14)") (class "Default")
      (node (ref "U6") (pin "14") (pinfunction "ISET_14") (pintype "passive+no_connect"))
    )
    (net (code "101") (name "unconnected-(U6-SYNCOUT-Pad9)") (class "Default")
      (node (ref "U6") (pin "9") (pinfunction "SYNCOUT_9") (pintype "passive+no_connect"))
    )
    (net (code "102") (name "unconnected-(U6-VSET-Pad13)") (class "Default")
      (node (ref "U6") (pin "13") (pinfunction "VSET_13") (pintype "passive+no_connect"))
    )
    (net (code "103") (name "unconnected-(X1-ST#-Pad1)") (class "Default")
      (node (ref "X1") (pin "1") (pinfunction "ST#_1") (pintype "passive+no_connect"))
    )
  )
)
